# mySatellite.net
KiCad netlist of a schematic drawn in EAGLE
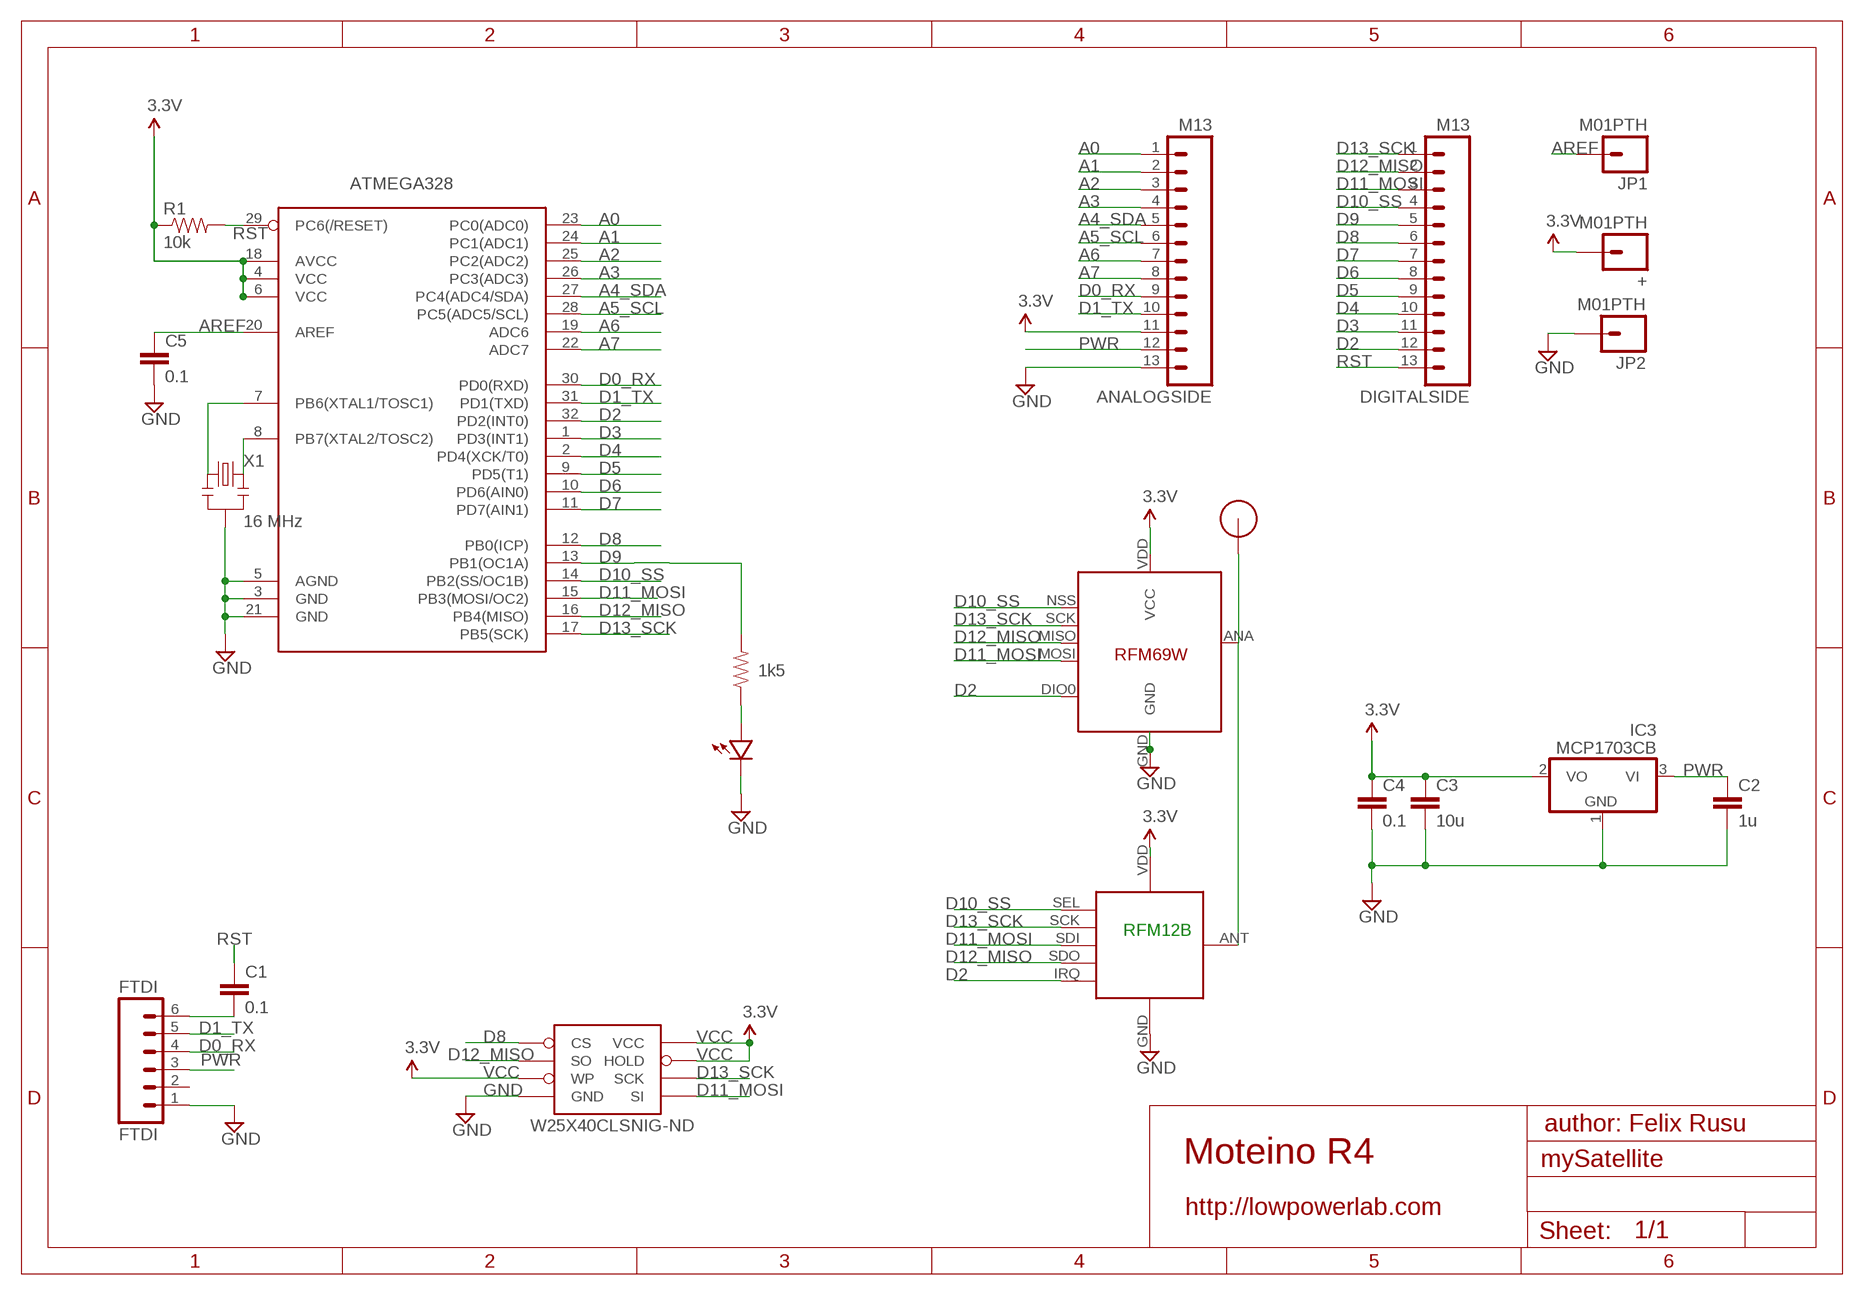
[diagram p0: schematic, sheet 1]

(export (version "E")
  (design (tool "Eeschema 10.0.6"))
  (components
    (comp (ref "+")
      (value "M01PTH")
      (footprint "eagle-import:1X01")
      (libsource (lib "eagle-import") (part "M01PTH"))
    )
    (comp (ref "ANALOGSIDE")
      (value "M13")
      (footprint "eagle-import:1X13")
      (libsource (lib "eagle-import") (part "M13"))
    )
    (comp (ref "ATMEGA328")
      (value "ATMega-328")
      (footprint "eagle-import:TQFP32-08")
      (libsource (lib "eagle-import") (part "ATMEGA168/328TQFP32"))
    )
    (comp (ref "C1")
      (value "0.1")
      (footprint "eagle-import:0603-CAP")
      (libsource (lib "eagle-import") (part "CAP0603-CAP"))
    )
    (comp (ref "C2")
      (value "1u")
      (footprint "eagle-import:0603-CAP")
      (libsource (lib "eagle-import") (part "CAP0603-CAP"))
    )
    (comp (ref "C3")
      (value "10u")
      (footprint "eagle-import:0805-CAP")
      (libsource (lib "eagle-import") (part "CAP0805-CAP"))
    )
    (comp (ref "C4")
      (value "0.1")
      (footprint "eagle-import:0603-CAP")
      (libsource (lib "eagle-import") (part "CAP0603-CAP"))
    )
    (comp (ref "C5")
      (value "0.1")
      (footprint "eagle-import:0603-CAP")
      (libsource (lib "eagle-import") (part "CAP0603-CAP"))
    )
    (comp (ref "DIGITALSIDE")
      (value "M13")
      (footprint "eagle-import:1X13")
      (libsource (lib "eagle-import") (part "M13"))
    )
    (comp (ref "FTDI")
      (value "FTDI")
      (footprint "eagle-import:1X06")
      (libsource (lib "eagle-import") (part "M06SIP"))
    )
    (comp (ref "IC3")
      (value "MCP1703CB")
      (footprint "eagle-import:SOT23")
      (libsource (lib "eagle-import") (part "MCP1703CB"))
    )
    (comp (ref "JP1")
      (value "M01PTH")
      (footprint "eagle-import:1X01")
      (libsource (lib "eagle-import") (part "M01PTH"))
    )
    (comp (ref "JP2")
      (value "M01PTH")
      (footprint "eagle-import:1X01")
      (libsource (lib "eagle-import") (part "M01PTH"))
    )
    (comp (ref "R1")
      (value "10k")
      (footprint "eagle-import:0603-RES")
      (libsource (lib "eagle-import") (part "RESISTOR0603-RES"))
    )
    (comp (ref "R2")
      (value "1k5")
      (footprint "eagle-import:0603-RES")
      (libsource (lib "eagle-import") (part "RESISTOR0603-RES"))
    )
    (comp (ref "RFM12B")
      (value "RFM12B_MINPADS")
      (footprint "eagle-import:RFM12B-MINPADS")
      (libsource (lib "eagle-import") (part "RFM12B_MINPADS"))
    )
    (comp (ref "U$1")
      (value "RFM12B_ANTENNA")
      (footprint "eagle-import:RFM12B-ANTENNA")
      (libsource (lib "eagle-import") (part "RFM12B_ANTENNA"))
    )
    (comp (ref "U$2")
      (value "LED0603")
      (footprint "eagle-import:0603-LED")
      (libsource (lib "eagle-import") (part "LED0603"))
    )
    (comp (ref "U$5")
      (value "RFM69")
      (footprint "eagle-import:RFM69W-MINPADS")
      (libsource (lib "eagle-import") (part "RFM69"))
    )
    (comp (ref "W25X40CLSNIG-ND")
      (value "AT25F512BWIDE_5.3MM")
      (footprint "eagle-import:SO08WIDE")
      (libsource (lib "eagle-import") (part "AT25F512BWIDE_5.3MM"))
    )
    (comp (ref "X1")
      (value "16 MHz")
      (footprint "eagle-import:RESONATOR-SMD")
      (libsource (lib "eagle-import") (part "RESONATORSMD"))
    )
  )
  (nets
    (net (code "1") (name "/A0") (class "Default")
      (node (ref "ANALOGSIDE") (pin "1") (pinfunction "1_1") (pintype "passive"))
      (node (ref "ATMEGA328") (pin "23") (pinfunction "PC0(ADC0)_23") (pintype "bidirectional"))
    )
    (net (code "2") (name "/A1") (class "Default")
      (node (ref "ANALOGSIDE") (pin "2") (pinfunction "2_2") (pintype "passive"))
      (node (ref "ATMEGA328") (pin "24") (pinfunction "PC1(ADC1)_24") (pintype "bidirectional"))
    )
    (net (code "3") (name "/A2") (class "Default")
      (node (ref "ANALOGSIDE") (pin "3") (pinfunction "3_3") (pintype "passive"))
      (node (ref "ATMEGA328") (pin "25") (pinfunction "PC2(ADC2)_25") (pintype "bidirectional"))
    )
    (net (code "4") (name "/A3") (class "Default")
      (node (ref "ANALOGSIDE") (pin "4") (pinfunction "4_4") (pintype "passive"))
      (node (ref "ATMEGA328") (pin "26") (pinfunction "PC3(ADC3)_26") (pintype "bidirectional"))
    )
    (net (code "5") (name "/A4_SDA") (class "Default")
      (node (ref "ANALOGSIDE") (pin "5") (pinfunction "5_5") (pintype "passive"))
      (node (ref "ATMEGA328") (pin "27") (pinfunction "PC4(ADC4/SDA)_27") (pintype "bidirectional"))
    )
    (net (code "6") (name "/A5_SCL") (class "Default")
      (node (ref "ANALOGSIDE") (pin "6") (pinfunction "6_6") (pintype "passive"))
      (node (ref "ATMEGA328") (pin "28") (pinfunction "PC5(ADC5/SCL)_28") (pintype "bidirectional"))
    )
    (net (code "7") (name "/A6") (class "Default")
      (node (ref "ANALOGSIDE") (pin "7") (pinfunction "7_7") (pintype "passive"))
      (node (ref "ATMEGA328") (pin "19") (pinfunction "ADC6_19") (pintype "bidirectional"))
    )
    (net (code "8") (name "/A7") (class "Default")
      (node (ref "ANALOGSIDE") (pin "8") (pinfunction "8_8") (pintype "passive"))
      (node (ref "ATMEGA328") (pin "22") (pinfunction "ADC7_22") (pintype "bidirectional"))
    )
    (net (code "9") (name "/AREF") (class "Default")
      (node (ref "ATMEGA328") (pin "20") (pinfunction "AREF_20") (pintype "bidirectional"))
      (node (ref "C5") (pin "1") (pinfunction "1_1") (pintype "passive"))
      (node (ref "JP1") (pin "1") (pinfunction "1_1") (pintype "passive"))
    )
    (net (code "10") (name "/D0_RX") (class "Default")
      (node (ref "ANALOGSIDE") (pin "9") (pinfunction "9_9") (pintype "passive"))
      (node (ref "ATMEGA328") (pin "30") (pinfunction "PD0(RXD)_30") (pintype "bidirectional"))
      (node (ref "FTDI") (pin "4") (pinfunction "4_4") (pintype "passive"))
    )
    (net (code "11") (name "/D1_TX") (class "Default")
      (node (ref "ANALOGSIDE") (pin "10") (pinfunction "10_10") (pintype "passive"))
      (node (ref "ATMEGA328") (pin "31") (pinfunction "PD1(TXD)_31") (pintype "bidirectional"))
      (node (ref "FTDI") (pin "5") (pinfunction "5_5") (pintype "passive"))
    )
    (net (code "12") (name "/D2") (class "Default")
      (node (ref "ATMEGA328") (pin "32") (pinfunction "PD2(INT0)_32") (pintype "bidirectional"))
      (node (ref "DIGITALSIDE") (pin "12") (pinfunction "12_12") (pintype "passive"))
      (node (ref "RFM12B") (pin "IRQ") (pinfunction "IRQ_IRQ") (pintype "bidirectional"))
      (node (ref "U$5") (pin "DIO0") (pinfunction "DIO0_DIO0") (pintype "open_collector"))
    )
    (net (code "13") (name "/D3") (class "Default")
      (node (ref "ATMEGA328") (pin "1") (pinfunction "PD3(INT1)_1") (pintype "bidirectional"))
      (node (ref "DIGITALSIDE") (pin "11") (pinfunction "11_11") (pintype "passive"))
    )
    (net (code "14") (name "/D4") (class "Default")
      (node (ref "ATMEGA328") (pin "2") (pinfunction "PD4(XCK/T0)_2") (pintype "bidirectional"))
      (node (ref "DIGITALSIDE") (pin "10") (pinfunction "10_10") (pintype "passive"))
    )
    (net (code "15") (name "/D5") (class "Default")
      (node (ref "ATMEGA328") (pin "9") (pinfunction "PD5(T1)_9") (pintype "bidirectional"))
      (node (ref "DIGITALSIDE") (pin "9") (pinfunction "9_9") (pintype "passive"))
    )
    (net (code "16") (name "/D6") (class "Default")
      (node (ref "ATMEGA328") (pin "10") (pinfunction "PD6(AIN0)_10") (pintype "bidirectional"))
      (node (ref "DIGITALSIDE") (pin "8") (pinfunction "8_8") (pintype "passive"))
    )
    (net (code "17") (name "/D7") (class "Default")
      (node (ref "ATMEGA328") (pin "11") (pinfunction "PD7(AIN1)_11") (pintype "bidirectional"))
      (node (ref "DIGITALSIDE") (pin "7") (pinfunction "7_7") (pintype "passive"))
    )
    (net (code "18") (name "/D8") (class "Default")
      (node (ref "ATMEGA328") (pin "12") (pinfunction "PB0(ICP)_12") (pintype "bidirectional"))
      (node (ref "DIGITALSIDE") (pin "6") (pinfunction "6_6") (pintype "passive"))
      (node (ref "W25X40CLSNIG-ND") (pin "1") (pinfunction "CS_1") (pintype "bidirectional"))
    )
    (net (code "19") (name "/D9") (class "Default")
      (node (ref "ATMEGA328") (pin "13") (pinfunction "PB1(OC1A)_13") (pintype "bidirectional"))
      (node (ref "DIGITALSIDE") (pin "5") (pinfunction "5_5") (pintype "passive"))
      (node (ref "R2") (pin "2") (pinfunction "2_2") (pintype "passive"))
    )
    (net (code "20") (name "/D10_SS") (class "Default")
      (node (ref "ATMEGA328") (pin "14") (pinfunction "PB2(SS/OC1B)_14") (pintype "bidirectional"))
      (node (ref "DIGITALSIDE") (pin "4") (pinfunction "4_4") (pintype "passive"))
      (node (ref "RFM12B") (pin "SEL") (pinfunction "SEL_SEL") (pintype "bidirectional"))
      (node (ref "U$5") (pin "NSS") (pinfunction "SEL_NSS") (pintype "input"))
    )
    (net (code "21") (name "/D11_MOSI") (class "Default")
      (node (ref "ATMEGA328") (pin "15") (pinfunction "PB3(MOSI/OC2)_15") (pintype "bidirectional"))
      (node (ref "DIGITALSIDE") (pin "3") (pinfunction "3_3") (pintype "passive"))
      (node (ref "RFM12B") (pin "SDI") (pinfunction "SDI/MOSI_SDI") (pintype "bidirectional"))
      (node (ref "U$5") (pin "MOSI") (pinfunction "MOSI_MOSI") (pintype "output"))
      (node (ref "W25X40CLSNIG-ND") (pin "5") (pinfunction "SI_5") (pintype "bidirectional"))
    )
    (net (code "22") (name "/D12_MISO") (class "Default")
      (node (ref "ATMEGA328") (pin "16") (pinfunction "PB4(MISO)_16") (pintype "bidirectional"))
      (node (ref "DIGITALSIDE") (pin "2") (pinfunction "2_2") (pintype "passive"))
      (node (ref "RFM12B") (pin "SDO") (pinfunction "SDO/MISO_SDO") (pintype "bidirectional"))
      (node (ref "U$5") (pin "MISO") (pinfunction "MISO_MISO") (pintype "input"))
      (node (ref "W25X40CLSNIG-ND") (pin "2") (pinfunction "SO_2") (pintype "bidirectional"))
    )
    (net (code "23") (name "/D13_SCK") (class "Default")
      (node (ref "ATMEGA328") (pin "17") (pinfunction "PB5(SCK)_17") (pintype "bidirectional"))
      (node (ref "DIGITALSIDE") (pin "1") (pinfunction "1_1") (pintype "passive"))
      (node (ref "RFM12B") (pin "SCK") (pinfunction "SCK_SCK") (pintype "bidirectional"))
      (node (ref "U$5") (pin "SCK") (pinfunction "SCK_SCK") (pintype "input"))
      (node (ref "W25X40CLSNIG-ND") (pin "6") (pinfunction "SCK_6") (pintype "bidirectional"))
    )
    (net (code "24") (name "/PWR") (class "Default")
      (node (ref "ANALOGSIDE") (pin "12") (pinfunction "12_12") (pintype "passive"))
      (node (ref "C2") (pin "1") (pinfunction "1_1") (pintype "passive"))
      (node (ref "FTDI") (pin "3") (pinfunction "3_3") (pintype "passive"))
      (node (ref "IC3") (pin "3") (pinfunction "VI_3") (pintype "input"))
    )
    (net (code "25") (name "/RST") (class "Default")
      (node (ref "ATMEGA328") (pin "29") (pinfunction "PC6(/RESET)_29") (pintype "bidirectional"))
      (node (ref "C1") (pin "1") (pinfunction "1_1") (pintype "passive"))
      (node (ref "DIGITALSIDE") (pin "13") (pinfunction "13_13") (pintype "passive"))
      (node (ref "R1") (pin "2") (pinfunction "2_2") (pintype "passive"))
    )
    (net (code "26") (name "3.3V") (class "Default")
      (node (ref "+") (pin "1") (pinfunction "1_1") (pintype "passive"))
      (node (ref "ANALOGSIDE") (pin "11") (pinfunction "11_11") (pintype "passive"))
      (node (ref "ATMEGA328") (pin "18") (pinfunction "AVCC_18") (pintype "bidirectional"))
      (node (ref "ATMEGA328") (pin "4") (pinfunction "VCC_4") (pintype "bidirectional"))
      (node (ref "ATMEGA328") (pin "6") (pinfunction "VCC_6") (pintype "bidirectional"))
      (node (ref "C3") (pin "1") (pinfunction "1_1") (pintype "passive"))
      (node (ref "C4") (pin "1") (pinfunction "1_1") (pintype "passive"))
      (node (ref "IC3") (pin "2") (pinfunction "VO_2") (pintype "passive"))
      (node (ref "R1") (pin "1") (pinfunction "1_1") (pintype "passive"))
      (node (ref "RFM12B") (pin "VDD") (pinfunction "VDD_VDD") (pintype "bidirectional"))
      (node (ref "U$5") (pin "VDD") (pinfunction "VCC_VDD") (pintype "power_in"))
      (node (ref "W25X40CLSNIG-ND") (pin "3") (pinfunction "WP_3") (pintype "bidirectional"))
      (node (ref "W25X40CLSNIG-ND") (pin "7") (pinfunction "HOLD_7") (pintype "bidirectional"))
      (node (ref "W25X40CLSNIG-ND") (pin "8") (pinfunction "VCC_8") (pintype "bidirectional"))
    )
    (net (code "27") (name "GND") (class "Default")
      (node (ref "ANALOGSIDE") (pin "13") (pinfunction "13_13") (pintype "passive"))
      (node (ref "ATMEGA328") (pin "21") (pinfunction "GND_21") (pintype "bidirectional"))
      (node (ref "ATMEGA328") (pin "3") (pinfunction "GND_3") (pintype "bidirectional"))
      (node (ref "ATMEGA328") (pin "5") (pinfunction "AGND_5") (pintype "bidirectional"))
      (node (ref "C2") (pin "2") (pinfunction "2_2") (pintype "passive"))
      (node (ref "C3") (pin "2") (pinfunction "2_2") (pintype "passive"))
      (node (ref "C4") (pin "2") (pinfunction "2_2") (pintype "passive"))
      (node (ref "C5") (pin "2") (pinfunction "2_2") (pintype "passive"))
      (node (ref "FTDI") (pin "1") (pinfunction "1_1") (pintype "passive"))
      (node (ref "IC3") (pin "1") (pinfunction "GND_1") (pintype "passive"))
      (node (ref "JP2") (pin "1") (pinfunction "1_1") (pintype "passive"))
      (node (ref "RFM12B") (pin "GND") (pinfunction "GND_GND") (pintype "bidirectional"))
      (node (ref "U$2") (pin "MINUS") (pinfunction "MINUS_MINUS") (pintype "passive"))
      (node (ref "U$5") (pin "GND") (pinfunction "GND_GND") (pintype "power_in"))
      (node (ref "W25X40CLSNIG-ND") (pin "4") (pinfunction "GND_4") (pintype "bidirectional"))
      (node (ref "X1") (pin "2") (pinfunction "2_2") (pintype "passive"))
    )
    (net (code "28") (name "Net-(ATMEGA328-PB6(XTAL1{slash}TOSC1))") (class "Default")
      (node (ref "ATMEGA328") (pin "7") (pinfunction "PB6(XTAL1/TOSC1)_7") (pintype "bidirectional"))
      (node (ref "X1") (pin "1") (pinfunction "1_1") (pintype "passive"))
    )
    (net (code "29") (name "Net-(ATMEGA328-PB7(XTAL2{slash}TOSC2))") (class "Default")
      (node (ref "ATMEGA328") (pin "8") (pinfunction "PB7(XTAL2/TOSC2)_8") (pintype "bidirectional"))
      (node (ref "X1") (pin "3") (pinfunction "3_3") (pintype "passive"))
    )
    (net (code "30") (name "Net-(C1-Pad2)") (class "Default")
      (node (ref "C1") (pin "2") (pinfunction "2_2") (pintype "passive"))
      (node (ref "FTDI") (pin "6") (pinfunction "6_6") (pintype "passive"))
    )
    (net (code "31") (name "Net-(R2-Pad1)") (class "Default")
      (node (ref "R2") (pin "1") (pinfunction "1_1") (pintype "passive"))
      (node (ref "U$2") (pin "PLUS") (pinfunction "PLUS_PLUS") (pintype "passive"))
    )
    (net (code "32") (name "Net-(U$1-1)") (class "Default")
      (node (ref "RFM12B") (pin "ANT") (pinfunction "ANT_ANT") (pintype "bidirectional"))
      (node (ref "U$1") (pin "P$1") (pinfunction "1_P$1") (pintype "bidirectional"))
      (node (ref "U$5") (pin "ANA") (pinfunction "ANT_ANA") (pintype "passive"))
    )
    (net (code "33") (name "unconnected-(FTDI-Pad2)") (class "Default")
      (node (ref "FTDI") (pin "2") (pinfunction "2_2") (pintype "passive"))
    )
  )
)
